# rfLED.net
KiCad netlist of a schematic drawn in EAGLE
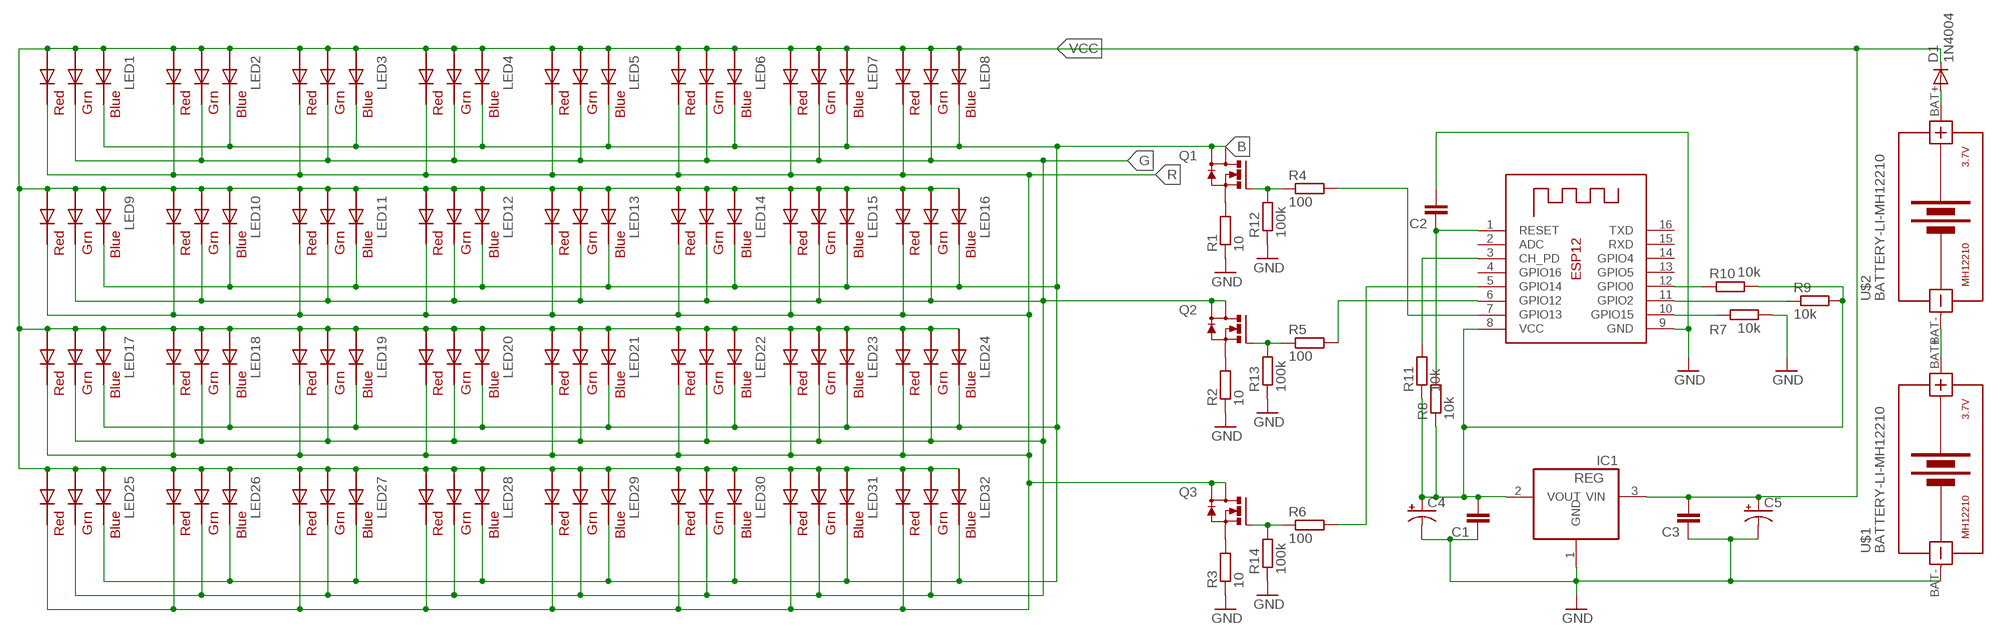
[diagram p0: schematic, sheet 1]

(export (version "E")
  (design (tool "Eeschema 10.0.6"))
  (components
    (comp (ref "C1") (value "C") (footprint "eagle-import:C0805") (libsource (lib "eagle-import") (part "C")))
    (comp (ref "C2") (value "C") (footprint "eagle-import:C0805") (libsource (lib "eagle-import") (part "C")))
    (comp (ref "C3") (value "C") (footprint "eagle-import:C0805") (libsource (lib "eagle-import") (part "C")))
    (comp (ref "C4")
      (value "CPOL-US150CLZ-1010")
      (footprint "eagle-import:150CLZ-1010")
      (libsource (lib "eagle-import") (part "CPOL-US150CLZ-1010"))
    )
    (comp (ref "C5")
      (value "CPOL-US150CLZ-1010")
      (footprint "eagle-import:150CLZ-1010")
      (libsource (lib "eagle-import") (part "CPOL-US150CLZ-1010"))
    )
    (comp (ref "D1")
      (value "1N4004")
      (footprint "eagle-import:DO41-10")
      (libsource (lib "eagle-import") (part "1N4004"))
    )
    (comp (ref "IC1")
      (value "REG")
      (footprint "eagle-import:SOT223")
      (fields (field (name "MPN") "REG1117"))
      (libsource (lib "eagle-import") (part "REG1117"))
    )
    (comp (ref "LED1")
      (value "RGBLED5050")
      (footprint "eagle-import:RGBLED5050")
      (libsource (lib "eagle-import") (part "RGBLED5050"))
    )
    (comp (ref "LED2")
      (value "RGBLED5050")
      (footprint "eagle-import:RGBLED5050")
      (libsource (lib "eagle-import") (part "RGBLED5050"))
    )
    (comp (ref "LED3")
      (value "RGBLED5050")
      (footprint "eagle-import:RGBLED5050")
      (libsource (lib "eagle-import") (part "RGBLED5050"))
    )
    (comp (ref "LED4")
      (value "RGBLED5050")
      (footprint "eagle-import:RGBLED5050")
      (libsource (lib "eagle-import") (part "RGBLED5050"))
    )
    (comp (ref "LED5")
      (value "RGBLED5050")
      (footprint "eagle-import:RGBLED5050")
      (libsource (lib "eagle-import") (part "RGBLED5050"))
    )
    (comp (ref "LED6")
      (value "RGBLED5050")
      (footprint "eagle-import:RGBLED5050")
      (libsource (lib "eagle-import") (part "RGBLED5050"))
    )
    (comp (ref "LED7")
      (value "RGBLED5050")
      (footprint "eagle-import:RGBLED5050")
      (libsource (lib "eagle-import") (part "RGBLED5050"))
    )
    (comp (ref "LED8")
      (value "RGBLED5050")
      (footprint "eagle-import:RGBLED5050")
      (libsource (lib "eagle-import") (part "RGBLED5050"))
    )
    (comp (ref "LED9")
      (value "RGBLED5050")
      (footprint "eagle-import:RGBLED5050")
      (libsource (lib "eagle-import") (part "RGBLED5050"))
    )
    (comp (ref "LED10")
      (value "RGBLED5050")
      (footprint "eagle-import:RGBLED5050")
      (libsource (lib "eagle-import") (part "RGBLED5050"))
    )
    (comp (ref "LED11")
      (value "RGBLED5050")
      (footprint "eagle-import:RGBLED5050")
      (libsource (lib "eagle-import") (part "RGBLED5050"))
    )
    (comp (ref "LED12")
      (value "RGBLED5050")
      (footprint "eagle-import:RGBLED5050")
      (libsource (lib "eagle-import") (part "RGBLED5050"))
    )
    (comp (ref "LED13")
      (value "RGBLED5050")
      (footprint "eagle-import:RGBLED5050")
      (libsource (lib "eagle-import") (part "RGBLED5050"))
    )
    (comp (ref "LED14")
      (value "RGBLED5050")
      (footprint "eagle-import:RGBLED5050")
      (libsource (lib "eagle-import") (part "RGBLED5050"))
    )
    (comp (ref "LED15")
      (value "RGBLED5050")
      (footprint "eagle-import:RGBLED5050")
      (libsource (lib "eagle-import") (part "RGBLED5050"))
    )
    (comp (ref "LED16")
      (value "RGBLED5050")
      (footprint "eagle-import:RGBLED5050")
      (libsource (lib "eagle-import") (part "RGBLED5050"))
    )
    (comp (ref "LED17")
      (value "RGBLED5050")
      (footprint "eagle-import:RGBLED5050")
      (libsource (lib "eagle-import") (part "RGBLED5050"))
    )
    (comp (ref "LED18")
      (value "RGBLED5050")
      (footprint "eagle-import:RGBLED5050")
      (libsource (lib "eagle-import") (part "RGBLED5050"))
    )
    (comp (ref "LED19")
      (value "RGBLED5050")
      (footprint "eagle-import:RGBLED5050")
      (libsource (lib "eagle-import") (part "RGBLED5050"))
    )
    (comp (ref "LED20")
      (value "RGBLED5050")
      (footprint "eagle-import:RGBLED5050")
      (libsource (lib "eagle-import") (part "RGBLED5050"))
    )
    (comp (ref "LED21")
      (value "RGBLED5050")
      (footprint "eagle-import:RGBLED5050")
      (libsource (lib "eagle-import") (part "RGBLED5050"))
    )
    (comp (ref "LED22")
      (value "RGBLED5050")
      (footprint "eagle-import:RGBLED5050")
      (libsource (lib "eagle-import") (part "RGBLED5050"))
    )
    (comp (ref "LED23")
      (value "RGBLED5050")
      (footprint "eagle-import:RGBLED5050")
      (libsource (lib "eagle-import") (part "RGBLED5050"))
    )
    (comp (ref "LED24")
      (value "RGBLED5050")
      (footprint "eagle-import:RGBLED5050")
      (libsource (lib "eagle-import") (part "RGBLED5050"))
    )
    (comp (ref "LED25")
      (value "RGBLED5050")
      (footprint "eagle-import:RGBLED5050")
      (libsource (lib "eagle-import") (part "RGBLED5050"))
    )
    (comp (ref "LED26")
      (value "RGBLED5050")
      (footprint "eagle-import:RGBLED5050")
      (libsource (lib "eagle-import") (part "RGBLED5050"))
    )
    (comp (ref "LED27")
      (value "RGBLED5050")
      (footprint "eagle-import:RGBLED5050")
      (libsource (lib "eagle-import") (part "RGBLED5050"))
    )
    (comp (ref "LED28")
      (value "RGBLED5050")
      (footprint "eagle-import:RGBLED5050")
      (libsource (lib "eagle-import") (part "RGBLED5050"))
    )
    (comp (ref "LED29")
      (value "RGBLED5050")
      (footprint "eagle-import:RGBLED5050")
      (libsource (lib "eagle-import") (part "RGBLED5050"))
    )
    (comp (ref "LED30")
      (value "RGBLED5050")
      (footprint "eagle-import:RGBLED5050")
      (libsource (lib "eagle-import") (part "RGBLED5050"))
    )
    (comp (ref "LED31")
      (value "RGBLED5050")
      (footprint "eagle-import:RGBLED5050")
      (libsource (lib "eagle-import") (part "RGBLED5050"))
    )
    (comp (ref "LED32")
      (value "RGBLED5050")
      (footprint "eagle-import:RGBLED5050")
      (libsource (lib "eagle-import") (part "RGBLED5050"))
    )
    (comp (ref "Q1")
      (value "MOSFET_N_SOT223")
      (footprint "eagle-import:SOT223")
      (libsource (lib "eagle-import") (part "MOSFET_N_SOT223"))
    )
    (comp (ref "Q2")
      (value "MOSFET_N_SOT223")
      (footprint "eagle-import:SOT223")
      (libsource (lib "eagle-import") (part "MOSFET_N_SOT223"))
    )
    (comp (ref "Q3")
      (value "MOSFET_N_SOT223")
      (footprint "eagle-import:SOT223")
      (libsource (lib "eagle-import") (part "MOSFET_N_SOT223"))
    )
    (comp (ref "R1")
      (value "10")
      (footprint "eagle-import:R2512")
      (libsource (lib "eagle-import") (part "RR2512"))
    )
    (comp (ref "R2")
      (value "10")
      (footprint "eagle-import:R2512")
      (libsource (lib "eagle-import") (part "RR2512"))
    )
    (comp (ref "R3")
      (value "10")
      (footprint "eagle-import:R2512")
      (libsource (lib "eagle-import") (part "RR2512"))
    )
    (comp (ref "R4")
      (value "100")
      (footprint "eagle-import:R1206")
      (libsource (lib "eagle-import") (part "RR1206"))
    )
    (comp (ref "R5")
      (value "100")
      (footprint "eagle-import:R1206")
      (libsource (lib "eagle-import") (part "RR1206"))
    )
    (comp (ref "R6")
      (value "100")
      (footprint "eagle-import:R1206")
      (libsource (lib "eagle-import") (part "RR1206"))
    )
    (comp (ref "R7")
      (value "10k")
      (footprint "eagle-import:R1206")
      (libsource (lib "eagle-import") (part "RR1206"))
    )
    (comp (ref "R8")
      (value "10k")
      (footprint "eagle-import:R1206")
      (libsource (lib "eagle-import") (part "RR1206"))
    )
    (comp (ref "R9")
      (value "10k")
      (footprint "eagle-import:R1206")
      (libsource (lib "eagle-import") (part "RR1206"))
    )
    (comp (ref "R10")
      (value "10k")
      (footprint "eagle-import:R1206")
      (libsource (lib "eagle-import") (part "RR1206"))
    )
    (comp (ref "R11")
      (value "10k")
      (footprint "eagle-import:R1206")
      (libsource (lib "eagle-import") (part "RR1206"))
    )
    (comp (ref "R12")
      (value "100k")
      (footprint "eagle-import:R1206")
      (libsource (lib "eagle-import") (part "RR1206"))
    )
    (comp (ref "R13")
      (value "100k")
      (footprint "eagle-import:R1206")
      (libsource (lib "eagle-import") (part "RR1206"))
    )
    (comp (ref "R14")
      (value "100k")
      (footprint "eagle-import:R1206")
      (libsource (lib "eagle-import") (part "RR1206"))
    )
    (comp (ref "U$1")
      (value "BATTERY-LI-MH12210")
      (footprint "eagle-import:BATTERY-LI-MH12210")
      (libsource (lib "eagle-import") (part "BATTERY-LI-MH12210"))
    )
    (comp (ref "U$2")
      (value "BATTERY-LI-MH12210")
      (footprint "eagle-import:BATTERY-LI-MH12210")
      (libsource (lib "eagle-import") (part "BATTERY-LI-MH12210"))
    )
    (comp (ref "X1")
      (value "ESP-12")
      (footprint "eagle-import:ESP-12")
      (libsource (lib "eagle-import") (part "ESP-12"))
    )
  )
  (nets
    (net (code "1") (name "B") (class "Default")
      (node (ref "LED1") (pin "4") (pinfunction "BLUE_C_4") (pintype "bidirectional"))
      (node (ref "LED10") (pin "4") (pinfunction "BLUE_C_4") (pintype "bidirectional"))
      (node (ref "LED11") (pin "4") (pinfunction "BLUE_C_4") (pintype "bidirectional"))
      (node (ref "LED12") (pin "4") (pinfunction "BLUE_C_4") (pintype "bidirectional"))
      (node (ref "LED13") (pin "4") (pinfunction "BLUE_C_4") (pintype "bidirectional"))
      (node (ref "LED14") (pin "4") (pinfunction "BLUE_C_4") (pintype "bidirectional"))
      (node (ref "LED15") (pin "4") (pinfunction "BLUE_C_4") (pintype "bidirectional"))
      (node (ref "LED16") (pin "4") (pinfunction "BLUE_C_4") (pintype "bidirectional"))
      (node (ref "LED17") (pin "4") (pinfunction "BLUE_C_4") (pintype "bidirectional"))
      (node (ref "LED18") (pin "4") (pinfunction "BLUE_C_4") (pintype "bidirectional"))
      (node (ref "LED19") (pin "4") (pinfunction "BLUE_C_4") (pintype "bidirectional"))
      (node (ref "LED2") (pin "4") (pinfunction "BLUE_C_4") (pintype "bidirectional"))
      (node (ref "LED20") (pin "4") (pinfunction "BLUE_C_4") (pintype "bidirectional"))
      (node (ref "LED21") (pin "4") (pinfunction "BLUE_C_4") (pintype "bidirectional"))
      (node (ref "LED22") (pin "4") (pinfunction "BLUE_C_4") (pintype "bidirectional"))
      (node (ref "LED23") (pin "4") (pinfunction "BLUE_C_4") (pintype "bidirectional"))
      (node (ref "LED24") (pin "4") (pinfunction "BLUE_C_4") (pintype "bidirectional"))
      (node (ref "LED25") (pin "4") (pinfunction "BLUE_C_4") (pintype "bidirectional"))
      (node (ref "LED26") (pin "4") (pinfunction "BLUE_C_4") (pintype "bidirectional"))
      (node (ref "LED27") (pin "4") (pinfunction "BLUE_C_4") (pintype "bidirectional"))
      (node (ref "LED28") (pin "4") (pinfunction "BLUE_C_4") (pintype "bidirectional"))
      (node (ref "LED29") (pin "4") (pinfunction "BLUE_C_4") (pintype "bidirectional"))
      (node (ref "LED3") (pin "4") (pinfunction "BLUE_C_4") (pintype "bidirectional"))
      (node (ref "LED30") (pin "4") (pinfunction "BLUE_C_4") (pintype "bidirectional"))
      (node (ref "LED31") (pin "4") (pinfunction "BLUE_C_4") (pintype "bidirectional"))
      (node (ref "LED32") (pin "4") (pinfunction "BLUE_C_4") (pintype "bidirectional"))
      (node (ref "LED4") (pin "4") (pinfunction "BLUE_C_4") (pintype "bidirectional"))
      (node (ref "LED5") (pin "4") (pinfunction "BLUE_C_4") (pintype "bidirectional"))
      (node (ref "LED6") (pin "4") (pinfunction "BLUE_C_4") (pintype "bidirectional"))
      (node (ref "LED7") (pin "4") (pinfunction "BLUE_C_4") (pintype "bidirectional"))
      (node (ref "LED8") (pin "4") (pinfunction "BLUE_C_4") (pintype "bidirectional"))
      (node (ref "LED9") (pin "4") (pinfunction "BLUE_C_4") (pintype "bidirectional"))
      (node (ref "Q1") (pin "2") (pinfunction "D_2") (pintype "passive"))
      (node (ref "Q1") (pin "4") (pinfunction "D1_4") (pintype "passive"))
    )
    (net (code "2") (name "G") (class "Default")
      (node (ref "LED1") (pin "6") (pinfunction "GREEN_C_6") (pintype "bidirectional"))
      (node (ref "LED10") (pin "6") (pinfunction "GREEN_C_6") (pintype "bidirectional"))
      (node (ref "LED11") (pin "6") (pinfunction "GREEN_C_6") (pintype "bidirectional"))
      (node (ref "LED12") (pin "6") (pinfunction "GREEN_C_6") (pintype "bidirectional"))
      (node (ref "LED13") (pin "6") (pinfunction "GREEN_C_6") (pintype "bidirectional"))
      (node (ref "LED14") (pin "6") (pinfunction "GREEN_C_6") (pintype "bidirectional"))
      (node (ref "LED15") (pin "6") (pinfunction "GREEN_C_6") (pintype "bidirectional"))
      (node (ref "LED16") (pin "6") (pinfunction "GREEN_C_6") (pintype "bidirectional"))
      (node (ref "LED17") (pin "6") (pinfunction "GREEN_C_6") (pintype "bidirectional"))
      (node (ref "LED18") (pin "6") (pinfunction "GREEN_C_6") (pintype "bidirectional"))
      (node (ref "LED19") (pin "6") (pinfunction "GREEN_C_6") (pintype "bidirectional"))
      (node (ref "LED2") (pin "6") (pinfunction "GREEN_C_6") (pintype "bidirectional"))
      (node (ref "LED20") (pin "6") (pinfunction "GREEN_C_6") (pintype "bidirectional"))
      (node (ref "LED21") (pin "6") (pinfunction "GREEN_C_6") (pintype "bidirectional"))
      (node (ref "LED22") (pin "6") (pinfunction "GREEN_C_6") (pintype "bidirectional"))
      (node (ref "LED23") (pin "6") (pinfunction "GREEN_C_6") (pintype "bidirectional"))
      (node (ref "LED24") (pin "6") (pinfunction "GREEN_C_6") (pintype "bidirectional"))
      (node (ref "LED25") (pin "6") (pinfunction "GREEN_C_6") (pintype "bidirectional"))
      (node (ref "LED26") (pin "6") (pinfunction "GREEN_C_6") (pintype "bidirectional"))
      (node (ref "LED27") (pin "6") (pinfunction "GREEN_C_6") (pintype "bidirectional"))
      (node (ref "LED28") (pin "6") (pinfunction "GREEN_C_6") (pintype "bidirectional"))
      (node (ref "LED29") (pin "6") (pinfunction "GREEN_C_6") (pintype "bidirectional"))
      (node (ref "LED3") (pin "6") (pinfunction "GREEN_C_6") (pintype "bidirectional"))
      (node (ref "LED30") (pin "6") (pinfunction "GREEN_C_6") (pintype "bidirectional"))
      (node (ref "LED31") (pin "6") (pinfunction "GREEN_C_6") (pintype "bidirectional"))
      (node (ref "LED32") (pin "6") (pinfunction "GREEN_C_6") (pintype "bidirectional"))
      (node (ref "LED4") (pin "6") (pinfunction "GREEN_C_6") (pintype "bidirectional"))
      (node (ref "LED5") (pin "6") (pinfunction "GREEN_C_6") (pintype "bidirectional"))
      (node (ref "LED6") (pin "6") (pinfunction "GREEN_C_6") (pintype "bidirectional"))
      (node (ref "LED7") (pin "6") (pinfunction "GREEN_C_6") (pintype "bidirectional"))
      (node (ref "LED8") (pin "6") (pinfunction "GREEN_C_6") (pintype "bidirectional"))
      (node (ref "LED9") (pin "6") (pinfunction "GREEN_C_6") (pintype "bidirectional"))
      (node (ref "Q2") (pin "2") (pinfunction "D_2") (pintype "passive"))
      (node (ref "Q2") (pin "4") (pinfunction "D1_4") (pintype "passive"))
    )
    (net (code "3") (name "GND") (class "Default")
      (node (ref "C1") (pin "1") (pinfunction "1_1") (pintype "passive"))
      (node (ref "C2") (pin "2") (pinfunction "2_2") (pintype "passive"))
      (node (ref "C3") (pin "1") (pinfunction "1_1") (pintype "passive"))
      (node (ref "C4") (pin "-") (pinfunction "-_-") (pintype "passive"))
      (node (ref "C5") (pin "-") (pinfunction "-_-") (pintype "passive"))
      (node (ref "IC1") (pin "1") (pinfunction "GND_1") (pintype "power_in"))
      (node (ref "R1") (pin "1") (pinfunction "1_1") (pintype "passive"))
      (node (ref "R12") (pin "1") (pinfunction "1_1") (pintype "passive"))
      (node (ref "R13") (pin "1") (pinfunction "1_1") (pintype "passive"))
      (node (ref "R14") (pin "1") (pinfunction "1_1") (pintype "passive"))
      (node (ref "R2") (pin "1") (pinfunction "1_1") (pintype "passive"))
      (node (ref "R3") (pin "1") (pinfunction "1_1") (pintype "passive"))
      (node (ref "R7") (pin "2") (pinfunction "2_2") (pintype "passive"))
      (node (ref "U$1") (pin "BAT-") (pinfunction "BAT-_BAT-") (pintype "power_in"))
      (node (ref "X1") (pin "9") (pinfunction "GND_9") (pintype "power_in"))
    )
    (net (code "4") (name "Net-(D1-PadA)") (class "Default")
      (node (ref "D1") (pin "A") (pinfunction "A_A") (pintype "passive"))
      (node (ref "U$2") (pin "BAT+") (pinfunction "BAT+_BAT+") (pintype "power_in"))
    )
    (net (code "5") (name "Net-(IC1-VOUT)") (class "Default")
      (node (ref "C1") (pin "2") (pinfunction "2_2") (pintype "passive"))
      (node (ref "C4") (pin "+") (pinfunction "+_+") (pintype "passive"))
      (node (ref "IC1") (pin "2") (pinfunction "VOUT_2") (pintype "output"))
      (node (ref "R10") (pin "2") (pinfunction "2_2") (pintype "passive"))
      (node (ref "R11") (pin "1") (pinfunction "1_1") (pintype "passive"))
      (node (ref "R8") (pin "1") (pinfunction "1_1") (pintype "passive"))
      (node (ref "R9") (pin "2") (pinfunction "2_2") (pintype "passive"))
      (node (ref "X1") (pin "8") (pinfunction "VCC_8") (pintype "power_in"))
    )
    (net (code "6") (name "Net-(Q1-G)") (class "Default")
      (node (ref "Q1") (pin "1") (pinfunction "G_1") (pintype "passive"))
      (node (ref "R12") (pin "2") (pinfunction "2_2") (pintype "passive"))
      (node (ref "R4") (pin "1") (pinfunction "1_1") (pintype "passive"))
    )
    (net (code "7") (name "Net-(Q1-S)") (class "Default")
      (node (ref "Q1") (pin "3") (pinfunction "S_3") (pintype "passive"))
      (node (ref "R1") (pin "2") (pinfunction "2_2") (pintype "passive"))
    )
    (net (code "8") (name "Net-(Q2-G)") (class "Default")
      (node (ref "Q2") (pin "1") (pinfunction "G_1") (pintype "passive"))
      (node (ref "R13") (pin "2") (pinfunction "2_2") (pintype "passive"))
      (node (ref "R5") (pin "1") (pinfunction "1_1") (pintype "passive"))
    )
    (net (code "9") (name "Net-(Q2-S)") (class "Default")
      (node (ref "Q2") (pin "3") (pinfunction "S_3") (pintype "passive"))
      (node (ref "R2") (pin "2") (pinfunction "2_2") (pintype "passive"))
    )
    (net (code "10") (name "Net-(Q3-G)") (class "Default")
      (node (ref "Q3") (pin "1") (pinfunction "G_1") (pintype "passive"))
      (node (ref "R14") (pin "2") (pinfunction "2_2") (pintype "passive"))
      (node (ref "R6") (pin "1") (pinfunction "1_1") (pintype "passive"))
    )
    (net (code "11") (name "Net-(Q3-S)") (class "Default")
      (node (ref "Q3") (pin "3") (pinfunction "S_3") (pintype "passive"))
      (node (ref "R3") (pin "2") (pinfunction "2_2") (pintype "passive"))
    )
    (net (code "12") (name "Net-(U$1-PadBAT+)") (class "Default")
      (node (ref "U$1") (pin "BAT+") (pinfunction "BAT+_BAT+") (pintype "power_in"))
      (node (ref "U$2") (pin "BAT-") (pinfunction "BAT-_BAT-") (pintype "power_in"))
    )
    (net (code "13") (name "Net-(X1-CH_PD)") (class "Default")
      (node (ref "R11") (pin "2") (pinfunction "2_2") (pintype "passive"))
      (node (ref "X1") (pin "3") (pinfunction "CH_PD_3") (pintype "input"))
    )
    (net (code "14") (name "Net-(X1-GPIO0)") (class "Default")
      (node (ref "R10") (pin "1") (pinfunction "1_1") (pintype "passive"))
      (node (ref "X1") (pin "12") (pinfunction "GPIO0_12") (pintype "bidirectional"))
    )
    (net (code "15") (name "Net-(X1-GPIO2)") (class "Default")
      (node (ref "R9") (pin "1") (pinfunction "1_1") (pintype "passive"))
      (node (ref "X1") (pin "11") (pinfunction "GPIO2_11") (pintype "bidirectional"))
    )
    (net (code "16") (name "Net-(X1-GPIO12)") (class "Default")
      (node (ref "R5") (pin "2") (pinfunction "2_2") (pintype "passive"))
      (node (ref "X1") (pin "6") (pinfunction "GPIO12_6") (pintype "bidirectional"))
    )
    (net (code "17") (name "Net-(X1-GPIO13)") (class "Default")
      (node (ref "R4") (pin "2") (pinfunction "2_2") (pintype "passive"))
      (node (ref "X1") (pin "7") (pinfunction "GPIO13_7") (pintype "bidirectional"))
    )
    (net (code "18") (name "Net-(X1-GPIO14)") (class "Default")
      (node (ref "R6") (pin "2") (pinfunction "2_2") (pintype "passive"))
      (node (ref "X1") (pin "5") (pinfunction "GPIO14_5") (pintype "bidirectional"))
    )
    (net (code "19") (name "Net-(X1-GPIO15)") (class "Default")
      (node (ref "R7") (pin "1") (pinfunction "1_1") (pintype "passive"))
      (node (ref "X1") (pin "10") (pinfunction "GPIO15_10") (pintype "bidirectional"))
    )
    (net (code "20") (name "Net-(X1-RESET)") (class "Default")
      (node (ref "C2") (pin "1") (pinfunction "1_1") (pintype "passive"))
      (node (ref "R8") (pin "2") (pinfunction "2_2") (pintype "passive"))
      (node (ref "X1") (pin "1") (pinfunction "RESET_1") (pintype "input"))
    )
    (net (code "21") (name "R") (class "Default")
      (node (ref "LED1") (pin "5") (pinfunction "RED_C_5") (pintype "bidirectional"))
      (node (ref "LED10") (pin "5") (pinfunction "RED_C_5") (pintype "bidirectional"))
      (node (ref "LED11") (pin "5") (pinfunction "RED_C_5") (pintype "bidirectional"))
      (node (ref "LED12") (pin "5") (pinfunction "RED_C_5") (pintype "bidirectional"))
      (node (ref "LED13") (pin "5") (pinfunction "RED_C_5") (pintype "bidirectional"))
      (node (ref "LED14") (pin "5") (pinfunction "RED_C_5") (pintype "bidirectional"))
      (node (ref "LED15") (pin "5") (pinfunction "RED_C_5") (pintype "bidirectional"))
      (node (ref "LED16") (pin "5") (pinfunction "RED_C_5") (pintype "bidirectional"))
      (node (ref "LED17") (pin "5") (pinfunction "RED_C_5") (pintype "bidirectional"))
      (node (ref "LED18") (pin "5") (pinfunction "RED_C_5") (pintype "bidirectional"))
      (node (ref "LED19") (pin "5") (pinfunction "RED_C_5") (pintype "bidirectional"))
      (node (ref "LED2") (pin "5") (pinfunction "RED_C_5") (pintype "bidirectional"))
      (node (ref "LED20") (pin "5") (pinfunction "RED_C_5") (pintype "bidirectional"))
      (node (ref "LED21") (pin "5") (pinfunction "RED_C_5") (pintype "bidirectional"))
      (node (ref "LED22") (pin "5") (pinfunction "RED_C_5") (pintype "bidirectional"))
      (node (ref "LED23") (pin "5") (pinfunction "RED_C_5") (pintype "bidirectional"))
      (node (ref "LED24") (pin "5") (pinfunction "RED_C_5") (pintype "bidirectional"))
      (node (ref "LED25") (pin "5") (pinfunction "RED_C_5") (pintype "bidirectional"))
      (node (ref "LED26") (pin "5") (pinfunction "RED_C_5") (pintype "bidirectional"))
      (node (ref "LED27") (pin "5") (pinfunction "RED_C_5") (pintype "bidirectional"))
      (node (ref "LED28") (pin "5") (pinfunction "RED_C_5") (pintype "bidirectional"))
      (node (ref "LED29") (pin "5") (pinfunction "RED_C_5") (pintype "bidirectional"))
      (node (ref "LED3") (pin "5") (pinfunction "RED_C_5") (pintype "bidirectional"))
      (node (ref "LED30") (pin "5") (pinfunction "RED_C_5") (pintype "bidirectional"))
      (node (ref "LED31") (pin "5") (pinfunction "RED_C_5") (pintype "bidirectional"))
      (node (ref "LED32") (pin "5") (pinfunction "RED_C_5") (pintype "bidirectional"))
      (node (ref "LED4") (pin "5") (pinfunction "RED_C_5") (pintype "bidirectional"))
      (node (ref "LED5") (pin "5") (pinfunction "RED_C_5") (pintype "bidirectional"))
      (node (ref "LED6") (pin "5") (pinfunction "RED_C_5") (pintype "bidirectional"))
      (node (ref "LED7") (pin "5") (pinfunction "RED_C_5") (pintype "bidirectional"))
      (node (ref "LED8") (pin "5") (pinfunction "RED_C_5") (pintype "bidirectional"))
      (node (ref "LED9") (pin "5") (pinfunction "RED_C_5") (pintype "bidirectional"))
      (node (ref "Q3") (pin "2") (pinfunction "D_2") (pintype "passive"))
      (node (ref "Q3") (pin "4") (pinfunction "D1_4") (pintype "passive"))
    )
    (net (code "22") (name "VCC") (class "Default")
      (node (ref "C3") (pin "2") (pinfunction "2_2") (pintype "passive"))
      (node (ref "C5") (pin "+") (pinfunction "+_+") (pintype "passive"))
      (node (ref "D1") (pin "C") (pinfunction "C_C") (pintype "passive"))
      (node (ref "IC1") (pin "3") (pinfunction "VIN_3") (pintype "input"))
      (node (ref "LED1") (pin "1") (pinfunction "GREEN_A_1") (pintype "bidirectional"))
      (node (ref "LED1") (pin "2") (pinfunction "RED_A_2") (pintype "bidirectional"))
      (node (ref "LED1") (pin "3") (pinfunction "BLUE_A_3") (pintype "bidirectional"))
      (node (ref "LED10") (pin "1") (pinfunction "GREEN_A_1") (pintype "bidirectional"))
      (node (ref "LED10") (pin "2") (pinfunction "RED_A_2") (pintype "bidirectional"))
      (node (ref "LED10") (pin "3") (pinfunction "BLUE_A_3") (pintype "bidirectional"))
      (node (ref "LED11") (pin "1") (pinfunction "GREEN_A_1") (pintype "bidirectional"))
      (node (ref "LED11") (pin "2") (pinfunction "RED_A_2") (pintype "bidirectional"))
      (node (ref "LED11") (pin "3") (pinfunction "BLUE_A_3") (pintype "bidirectional"))
      (node (ref "LED12") (pin "1") (pinfunction "GREEN_A_1") (pintype "bidirectional"))
      (node (ref "LED12") (pin "2") (pinfunction "RED_A_2") (pintype "bidirectional"))
      (node (ref "LED12") (pin "3") (pinfunction "BLUE_A_3") (pintype "bidirectional"))
      (node (ref "LED13") (pin "1") (pinfunction "GREEN_A_1") (pintype "bidirectional"))
      (node (ref "LED13") (pin "2") (pinfunction "RED_A_2") (pintype "bidirectional"))
      (node (ref "LED13") (pin "3") (pinfunction "BLUE_A_3") (pintype "bidirectional"))
      (node (ref "LED14") (pin "1") (pinfunction "GREEN_A_1") (pintype "bidirectional"))
      (node (ref "LED14") (pin "2") (pinfunction "RED_A_2") (pintype "bidirectional"))
      (node (ref "LED14") (pin "3") (pinfunction "BLUE_A_3") (pintype "bidirectional"))
      (node (ref "LED15") (pin "1") (pinfunction "GREEN_A_1") (pintype "bidirectional"))
      (node (ref "LED15") (pin "2") (pinfunction "RED_A_2") (pintype "bidirectional"))
      (node (ref "LED15") (pin "3") (pinfunction "BLUE_A_3") (pintype "bidirectional"))
      (node (ref "LED16") (pin "1") (pinfunction "GREEN_A_1") (pintype "bidirectional"))
      (node (ref "LED16") (pin "2") (pinfunction "RED_A_2") (pintype "bidirectional"))
      (node (ref "LED16") (pin "3") (pinfunction "BLUE_A_3") (pintype "bidirectional"))
      (node (ref "LED17") (pin "1") (pinfunction "GREEN_A_1") (pintype "bidirectional"))
      (node (ref "LED17") (pin "2") (pinfunction "RED_A_2") (pintype "bidirectional"))
      (node (ref "LED17") (pin "3") (pinfunction "BLUE_A_3") (pintype "bidirectional"))
      (node (ref "LED18") (pin "1") (pinfunction "GREEN_A_1") (pintype "bidirectional"))
      (node (ref "LED18") (pin "2") (pinfunction "RED_A_2") (pintype "bidirectional"))
      (node (ref "LED18") (pin "3") (pinfunction "BLUE_A_3") (pintype "bidirectional"))
      (node (ref "LED19") (pin "1") (pinfunction "GREEN_A_1") (pintype "bidirectional"))
      (node (ref "LED19") (pin "2") (pinfunction "RED_A_2") (pintype "bidirectional"))
      (node (ref "LED19") (pin "3") (pinfunction "BLUE_A_3") (pintype "bidirectional"))
      (node (ref "LED2") (pin "1") (pinfunction "GREEN_A_1") (pintype "bidirectional"))
      (node (ref "LED2") (pin "2") (pinfunction "RED_A_2") (pintype "bidirectional"))
      (node (ref "LED2") (pin "3") (pinfunction "BLUE_A_3") (pintype "bidirectional"))
      (node (ref "LED20") (pin "1") (pinfunction "GREEN_A_1") (pintype "bidirectional"))
      (node (ref "LED20") (pin "2") (pinfunction "RED_A_2") (pintype "bidirectional"))
      (node (ref "LED20") (pin "3") (pinfunction "BLUE_A_3") (pintype "bidirectional"))
      (node (ref "LED21") (pin "1") (pinfunction "GREEN_A_1") (pintype "bidirectional"))
      (node (ref "LED21") (pin "2") (pinfunction "RED_A_2") (pintype "bidirectional"))
      (node (ref "LED21") (pin "3") (pinfunction "BLUE_A_3") (pintype "bidirectional"))
      (node (ref "LED22") (pin "1") (pinfunction "GREEN_A_1") (pintype "bidirectional"))
      (node (ref "LED22") (pin "2") (pinfunction "RED_A_2") (pintype "bidirectional"))
      (node (ref "LED22") (pin "3") (pinfunction "BLUE_A_3") (pintype "bidirectional"))
      (node (ref "LED23") (pin "1") (pinfunction "GREEN_A_1") (pintype "bidirectional"))
      (node (ref "LED23") (pin "2") (pinfunction "RED_A_2") (pintype "bidirectional"))
      (node (ref "LED23") (pin "3") (pinfunction "BLUE_A_3") (pintype "bidirectional"))
      (node (ref "LED24") (pin "1") (pinfunction "GREEN_A_1") (pintype "bidirectional"))
      (node (ref "LED24") (pin "2") (pinfunction "RED_A_2") (pintype "bidirectional"))
      (node (ref "LED24") (pin "3") (pinfunction "BLUE_A_3") (pintype "bidirectional"))
      (node (ref "LED25") (pin "1") (pinfunction "GREEN_A_1") (pintype "bidirectional"))
      (node (ref "LED25") (pin "2") (pinfunction "RED_A_2") (pintype "bidirectional"))
      (node (ref "LED25") (pin "3") (pinfunction "BLUE_A_3") (pintype "bidirectional"))
      (node (ref "LED26") (pin "1") (pinfunction "GREEN_A_1") (pintype "bidirectional"))
      (node (ref "LED26") (pin "2") (pinfunction "RED_A_2") (pintype "bidirectional"))
      (node (ref "LED26") (pin "3") (pinfunction "BLUE_A_3") (pintype "bidirectional"))
      (node (ref "LED27") (pin "1") (pinfunction "GREEN_A_1") (pintype "bidirectional"))
      (node (ref "LED27") (pin "2") (pinfunction "RED_A_2") (pintype "bidirectional"))
      (node (ref "LED27") (pin "3") (pinfunction "BLUE_A_3") (pintype "bidirectional"))
      (node (ref "LED28") (pin "1") (pinfunction "GREEN_A_1") (pintype "bidirectional"))
      (node (ref "LED28") (pin "2") (pinfunction "RED_A_2") (pintype "bidirectional"))
      (node (ref "LED28") (pin "3") (pinfunction "BLUE_A_3") (pintype "bidirectional"))
      (node (ref "LED29") (pin "1") (pinfunction "GREEN_A_1") (pintype "bidirectional"))
      (node (ref "LED29") (pin "2") (pinfunction "RED_A_2") (pintype "bidirectional"))
      (node (ref "LED29") (pin "3") (pinfunction "BLUE_A_3") (pintype "bidirectional"))
      (node (ref "LED3") (pin "1") (pinfunction "GREEN_A_1") (pintype "bidirectional"))
      (node (ref "LED3") (pin "2") (pinfunction "RED_A_2") (pintype "bidirectional"))
      (node (ref "LED3") (pin "3") (pinfunction "BLUE_A_3") (pintype "bidirectional"))
      (node (ref "LED30") (pin "1") (pinfunction "GREEN_A_1") (pintype "bidirectional"))
      (node (ref "LED30") (pin "2") (pinfunction "RED_A_2") (pintype "bidirectional"))
      (node (ref "LED30") (pin "3") (pinfunction "BLUE_A_3") (pintype "bidirectional"))
      (node (ref "LED31") (pin "1") (pinfunction "GREEN_A_1") (pintype "bidirectional"))
      (node (ref "LED31") (pin "2") (pinfunction "RED_A_2") (pintype "bidirectional"))
      (node (ref "LED31") (pin "3") (pinfunction "BLUE_A_3") (pintype "bidirectional"))
      (node (ref "LED32") (pin "1") (pinfunction "GREEN_A_1") (pintype "bidirectional"))
      (node (ref "LED32") (pin "2") (pinfunction "RED_A_2") (pintype "bidirectional"))
      (node (ref "LED32") (pin "3") (pinfunction "BLUE_A_3") (pintype "bidirectional"))
      (node (ref "LED4") (pin "1") (pinfunction "GREEN_A_1") (pintype "bidirectional"))
      (node (ref "LED4") (pin "2") (pinfunction "RED_A_2") (pintype "bidirectional"))
      (node (ref "LED4") (pin "3") (pinfunction "BLUE_A_3") (pintype "bidirectional"))
      (node (ref "LED5") (pin "1") (pinfunction "GREEN_A_1") (pintype "bidirectional"))
      (node (ref "LED5") (pin "2") (pinfunction "RED_A_2") (pintype "bidirectional"))
      (node (ref "LED5") (pin "3") (pinfunction "BLUE_A_3") (pintype "bidirectional"))
      (node (ref "LED6") (pin "1") (pinfunction "GREEN_A_1") (pintype "bidirectional"))
      (node (ref "LED6") (pin "2") (pinfunction "RED_A_2") (pintype "bidirectional"))
      (node (ref "LED6") (pin "3") (pinfunction "BLUE_A_3") (pintype "bidirectional"))
      (node (ref "LED7") (pin "1") (pinfunction "GREEN_A_1") (pintype "bidirectional"))
      (node (ref "LED7") (pin "2") (pinfunction "RED_A_2") (pintype "bidirectional"))
      (node (ref "LED7") (pin "3") (pinfunction "BLUE_A_3") (pintype "bidirectional"))
      (node (ref "LED8") (pin "1") (pinfunction "GREEN_A_1") (pintype "bidirectional"))
      (node (ref "LED8") (pin "2") (pinfunction "RED_A_2") (pintype "bidirectional"))
      (node (ref "LED8") (pin "3") (pinfunction "BLUE_A_3") (pintype "bidirectional"))
      (node (ref "LED9") (pin "1") (pinfunction "GREEN_A_1") (pintype "bidirectional"))
      (node (ref "LED9") (pin "2") (pinfunction "RED_A_2") (pintype "bidirectional"))
      (node (ref "LED9") (pin "3") (pinfunction "BLUE_A_3") (pintype "bidirectional"))
    )
    (net (code "23") (name "unconnected-(X1-ADC-Pad2)") (class "Default")
      (node (ref "X1") (pin "2") (pinfunction "ADC_2") (pintype "passive"))
    )
    (net (code "24") (name "unconnected-(X1-GPIO4-Pad14)") (class "Default")
      (node (ref "X1") (pin "14") (pinfunction "GPIO4_14") (pintype "bidirectional"))
    )
    (net (code "25") (name "unconnected-(X1-GPIO5-Pad13)") (class "Default")
      (node (ref "X1") (pin "13") (pinfunction "GPIO5_13") (pintype "bidirectional"))
    )
    (net (code "26") (name "unconnected-(X1-GPIO16-Pad4)") (class "Default")
      (node (ref "X1") (pin "4") (pinfunction "GPIO16_4") (pintype "bidirectional"))
    )
    (net (code "27") (name "unconnected-(X1-RXD-Pad15)") (class "Default")
      (node (ref "X1") (pin "15") (pinfunction "RXD_15") (pintype "input"))
    )
    (net (code "28") (name "unconnected-(X1-TXD-Pad16)") (class "Default")
      (node (ref "X1") (pin "16") (pinfunction "TXD_16") (pintype "output"))
    )
  )
)
